# Jumper_1_1.net
KiCad netlist of a schematic drawn in EAGLE
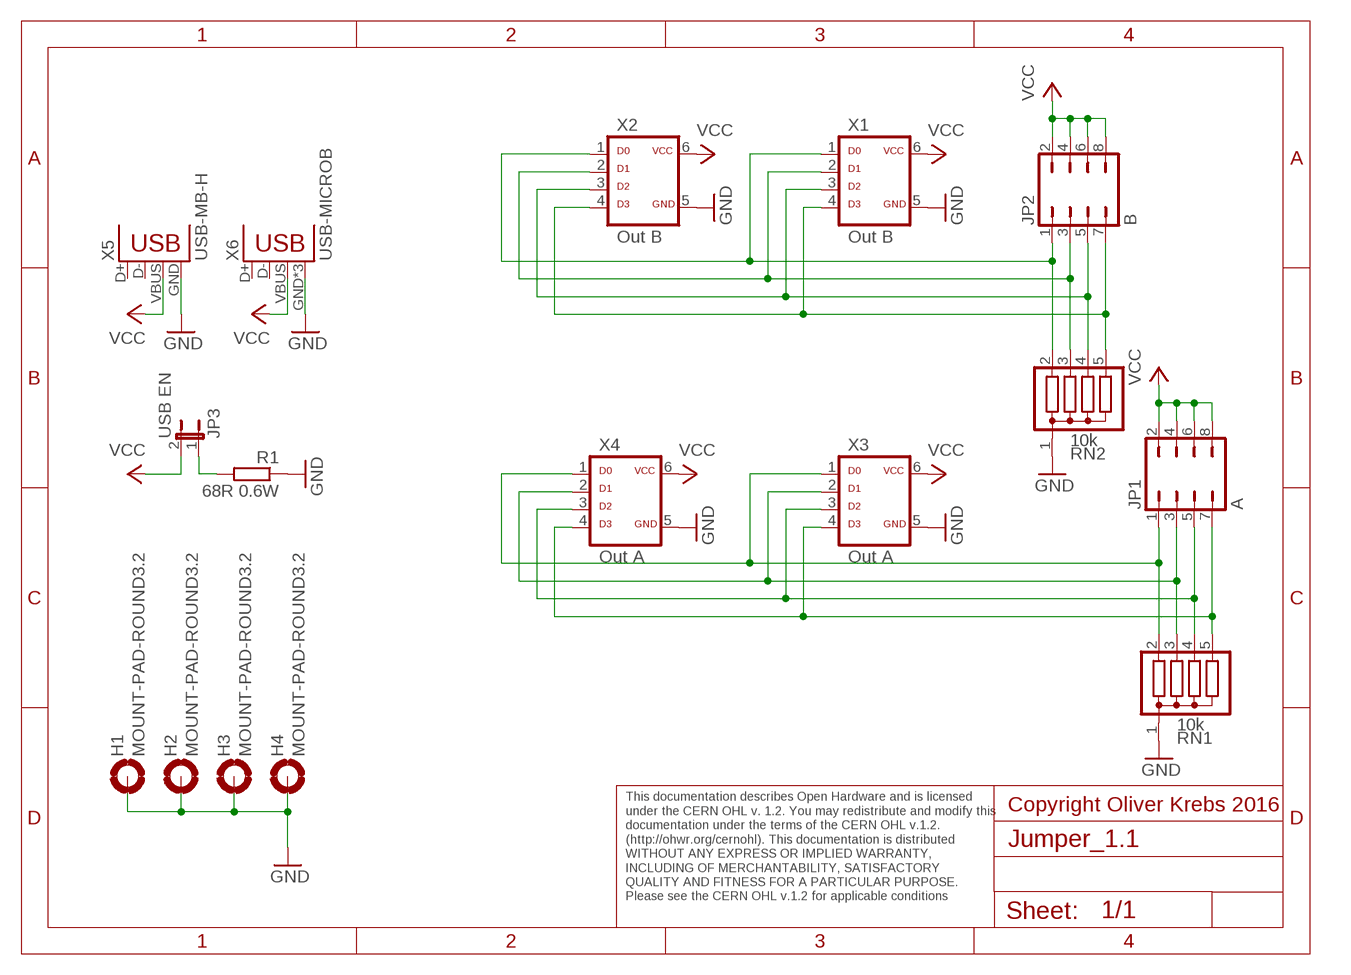
[diagram p0: schematic, sheet 1]

(export (version "E")
  (design (tool "Eeschema 10.0.6"))
  (components
    (comp (ref "H1")
      (value "MOUNT-PAD-ROUND3.2")
      (footprint "eagle-import:3,2-PAD")
      (libsource (lib "eagle-import") (part "MOUNT-PAD-ROUND3.2"))
    )
    (comp (ref "H2")
      (value "MOUNT-PAD-ROUND3.2")
      (footprint "eagle-import:3,2-PAD")
      (libsource (lib "eagle-import") (part "MOUNT-PAD-ROUND3.2"))
    )
    (comp (ref "H3")
      (value "MOUNT-PAD-ROUND3.2")
      (footprint "eagle-import:3,2-PAD")
      (libsource (lib "eagle-import") (part "MOUNT-PAD-ROUND3.2"))
    )
    (comp (ref "H4")
      (value "MOUNT-PAD-ROUND3.2")
      (footprint "eagle-import:3,2-PAD")
      (libsource (lib "eagle-import") (part "MOUNT-PAD-ROUND3.2"))
    )
    (comp (ref "JP1")
      (value "A")
      (footprint "eagle-import:JP4Q")
      (libsource (lib "eagle-import") (part "JP4Q"))
    )
    (comp (ref "JP2")
      (value "B")
      (footprint "eagle-import:JP4Q")
      (libsource (lib "eagle-import") (part "JP4Q"))
    )
    (comp (ref "JP3")
      (value "USB EN")
      (footprint "eagle-import:JP1")
      (libsource (lib "eagle-import") (part "JP1E"))
    )
    (comp (ref "R1")
      (value "68R 0.6W")
      (footprint "eagle-import:0207_10")
      (libsource (lib "eagle-import") (part "R-EU_0207/10"))
    )
    (comp (ref "RN1")
      (value "10k")
      (footprint "eagle-import:SIL5")
      (libsource (lib "eagle-import") (part "G04R"))
    )
    (comp (ref "RN2")
      (value "10k")
      (footprint "eagle-import:SIL5")
      (libsource (lib "eagle-import") (part "G04R"))
    )
    (comp (ref "X1")
      (value "Out B")
      (footprint "eagle-import:ML-6")
      (libsource (lib "eagle-import") (part "ML6D"))
    )
    (comp (ref "X2")
      (value "Out B")
      (footprint "eagle-import:ML-6")
      (libsource (lib "eagle-import") (part "ML6D"))
    )
    (comp (ref "X3")
      (value "Out A")
      (footprint "eagle-import:ML-6")
      (libsource (lib "eagle-import") (part "ML6D"))
    )
    (comp (ref "X4")
      (value "Out A")
      (footprint "eagle-import:ML-6")
      (libsource (lib "eagle-import") (part "ML6D"))
    )
    (comp (ref "X5")
      (value "USB-MB-H")
      (footprint "eagle-import:USB-MB-H")
      (libsource (lib "eagle-import") (part "USB-MB-H"))
    )
    (comp (ref "X6")
      (value "USB-MICROB")
      (footprint "eagle-import:USB-MICROB")
      (libsource (lib "eagle-import") (part "USB-MICROB"))
    )
  )
  (nets
    (net (code "1") (name "GND") (class "Default")
      (node (ref "H1") (pin "B3,2") (pinfunction "MOUNT_B3,2") (pintype "passive"))
      (node (ref "H2") (pin "B3,2") (pinfunction "MOUNT_B3,2") (pintype "passive"))
      (node (ref "H3") (pin "B3,2") (pinfunction "MOUNT_B3,2") (pintype "passive"))
      (node (ref "H4") (pin "B3,2") (pinfunction "MOUNT_B3,2") (pintype "passive"))
      (node (ref "R1") (pin "1") (pinfunction "1_1") (pintype "passive"))
      (node (ref "RN1") (pin "1") (pinfunction "1_1") (pintype "passive"))
      (node (ref "RN2") (pin "1") (pinfunction "1_1") (pintype "passive"))
      (node (ref "X1") (pin "5") (pinfunction "5_5") (pintype "passive"))
      (node (ref "X2") (pin "5") (pinfunction "5_5") (pintype "passive"))
      (node (ref "X3") (pin "5") (pinfunction "5_5") (pintype "passive"))
      (node (ref "X4") (pin "5") (pinfunction "5_5") (pintype "passive"))
      (node (ref "X5") (pin "GND") (pinfunction "GND_GND") (pintype "bidirectional"))
      (node (ref "X6") (pin "GND") (pinfunction "GND_GND") (pintype "bidirectional"))
      (node (ref "X6") (pin "MT1") (pinfunction "GND_MT1") (pintype "bidirectional"))
      (node (ref "X6") (pin "MT2") (pinfunction "GND_MT2") (pintype "bidirectional"))
    )
    (net (code "2") (name "Net-(JP1-Pad1)") (class "Default")
      (node (ref "JP1") (pin "1") (pinfunction "1_1") (pintype "passive"))
      (node (ref "RN1") (pin "2") (pinfunction "2_2") (pintype "passive"))
      (node (ref "X3") (pin "1") (pinfunction "1_1") (pintype "passive"))
      (node (ref "X4") (pin "1") (pinfunction "1_1") (pintype "passive"))
    )
    (net (code "3") (name "Net-(JP1-Pad3)") (class "Default")
      (node (ref "JP1") (pin "3") (pinfunction "3_3") (pintype "passive"))
      (node (ref "RN1") (pin "3") (pinfunction "3_3") (pintype "passive"))
      (node (ref "X3") (pin "2") (pinfunction "2_2") (pintype "passive"))
      (node (ref "X4") (pin "2") (pinfunction "2_2") (pintype "passive"))
    )
    (net (code "4") (name "Net-(JP1-Pad5)") (class "Default")
      (node (ref "JP1") (pin "5") (pinfunction "5_5") (pintype "passive"))
      (node (ref "RN1") (pin "4") (pinfunction "4_4") (pintype "passive"))
      (node (ref "X3") (pin "3") (pinfunction "3_3") (pintype "passive"))
      (node (ref "X4") (pin "3") (pinfunction "3_3") (pintype "passive"))
    )
    (net (code "5") (name "Net-(JP1-Pad7)") (class "Default")
      (node (ref "JP1") (pin "7") (pinfunction "7_7") (pintype "passive"))
      (node (ref "RN1") (pin "5") (pinfunction "5_5") (pintype "passive"))
      (node (ref "X3") (pin "4") (pinfunction "4_4") (pintype "passive"))
      (node (ref "X4") (pin "4") (pinfunction "4_4") (pintype "passive"))
    )
    (net (code "6") (name "Net-(JP2-Pad1)") (class "Default")
      (node (ref "JP2") (pin "1") (pinfunction "1_1") (pintype "passive"))
      (node (ref "RN2") (pin "2") (pinfunction "2_2") (pintype "passive"))
      (node (ref "X1") (pin "1") (pinfunction "1_1") (pintype "passive"))
      (node (ref "X2") (pin "1") (pinfunction "1_1") (pintype "passive"))
    )
    (net (code "7") (name "Net-(JP2-Pad3)") (class "Default")
      (node (ref "JP2") (pin "3") (pinfunction "3_3") (pintype "passive"))
      (node (ref "RN2") (pin "3") (pinfunction "3_3") (pintype "passive"))
      (node (ref "X1") (pin "2") (pinfunction "2_2") (pintype "passive"))
      (node (ref "X2") (pin "2") (pinfunction "2_2") (pintype "passive"))
    )
    (net (code "8") (name "Net-(JP2-Pad5)") (class "Default")
      (node (ref "JP2") (pin "5") (pinfunction "5_5") (pintype "passive"))
      (node (ref "RN2") (pin "4") (pinfunction "4_4") (pintype "passive"))
      (node (ref "X1") (pin "3") (pinfunction "3_3") (pintype "passive"))
      (node (ref "X2") (pin "3") (pinfunction "3_3") (pintype "passive"))
    )
    (net (code "9") (name "Net-(JP2-Pad7)") (class "Default")
      (node (ref "JP2") (pin "7") (pinfunction "7_7") (pintype "passive"))
      (node (ref "RN2") (pin "5") (pinfunction "5_5") (pintype "passive"))
      (node (ref "X1") (pin "4") (pinfunction "4_4") (pintype "passive"))
      (node (ref "X2") (pin "4") (pinfunction "4_4") (pintype "passive"))
    )
    (net (code "10") (name "Net-(JP3-Pad1)") (class "Default")
      (node (ref "JP3") (pin "1") (pinfunction "1_1") (pintype "passive"))
      (node (ref "R1") (pin "2") (pinfunction "2_2") (pintype "passive"))
    )
    (net (code "11") (name "VCC") (class "Default")
      (node (ref "JP1") (pin "2") (pinfunction "2_2") (pintype "passive"))
      (node (ref "JP1") (pin "4") (pinfunction "4_4") (pintype "passive"))
      (node (ref "JP1") (pin "6") (pinfunction "6_6") (pintype "passive"))
      (node (ref "JP1") (pin "8") (pinfunction "8_8") (pintype "passive"))
      (node (ref "JP2") (pin "2") (pinfunction "2_2") (pintype "passive"))
      (node (ref "JP2") (pin "4") (pinfunction "4_4") (pintype "passive"))
      (node (ref "JP2") (pin "6") (pinfunction "6_6") (pintype "passive"))
      (node (ref "JP2") (pin "8") (pinfunction "8_8") (pintype "passive"))
      (node (ref "JP3") (pin "2") (pinfunction "2_2") (pintype "passive"))
      (node (ref "X1") (pin "6") (pinfunction "6_6") (pintype "passive"))
      (node (ref "X2") (pin "6") (pinfunction "6_6") (pintype "passive"))
      (node (ref "X3") (pin "6") (pinfunction "6_6") (pintype "passive"))
      (node (ref "X4") (pin "6") (pinfunction "6_6") (pintype "passive"))
      (node (ref "X5") (pin "VBUS") (pinfunction "VBUS_VBUS") (pintype "bidirectional"))
      (node (ref "X6") (pin "VBUS") (pinfunction "VBUS_VBUS") (pintype "bidirectional"))
    )
    (net (code "12") (name "unconnected-(X5-PadD+)") (class "Default")
      (node (ref "X5") (pin "D+") (pinfunction "D+_D+") (pintype "bidirectional"))
    )
    (net (code "13") (name "unconnected-(X5-PadD-)") (class "Default")
      (node (ref "X5") (pin "D-") (pinfunction "D-_D-") (pintype "bidirectional"))
    )
    (net (code "14") (name "unconnected-(X6-PadD+)") (class "Default")
      (node (ref "X6") (pin "D+") (pinfunction "D+_D+") (pintype "bidirectional"))
    )
    (net (code "15") (name "unconnected-(X6-PadD-)") (class "Default")
      (node (ref "X6") (pin "D-") (pinfunction "D-_D-") (pintype "bidirectional"))
    )
  )
)
